# iTag3_sensors.net
KiCad netlist of a schematic drawn in Altium Designer
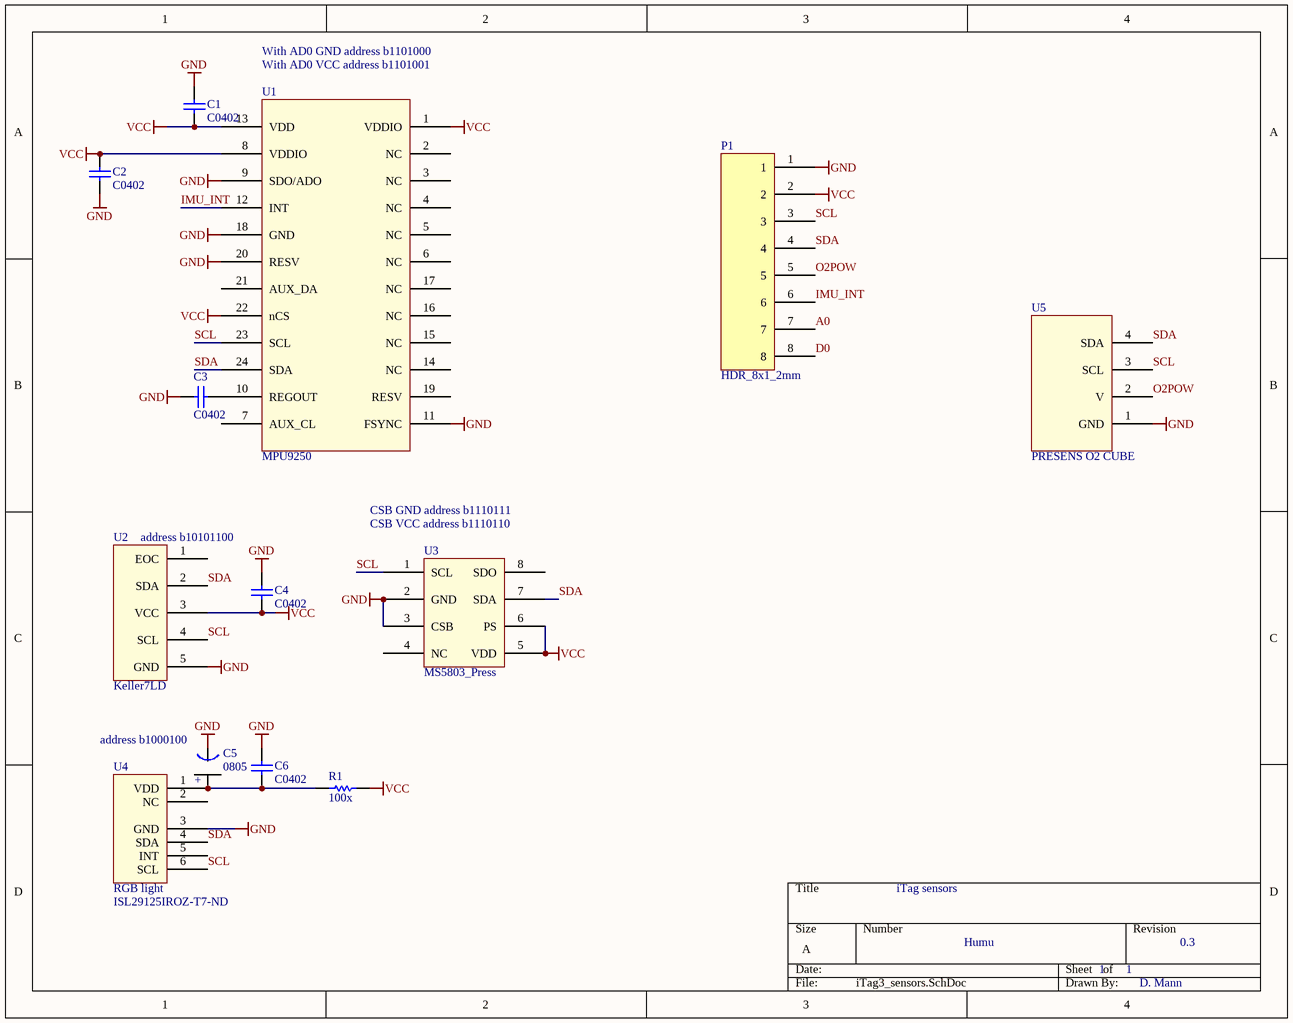
[diagram p0: iTag3_sensors.SchDoc]

(export (version "E")
  (design (tool "Eeschema 10.0.6"))
  (components
    (comp (ref "C1")
      (value "C0402")
      (footprint "0402")
      (description "Ceramic Chip Capacitor - Standard")
      (fields (field (name "PUBLISHER") "Altium Limited"))
      (libsource (lib "KEMET Chip Capacitor") (part "C0402"))
    )
    (comp (ref "C2")
      (value "C0402")
      (footprint "0402")
      (description "Ceramic Chip Capacitor - Standard")
      (fields (field (name "PUBLISHER") "Altium Limited"))
      (libsource (lib "KEMET Chip Capacitor") (part "C0402"))
    )
    (comp (ref "C3")
      (value "C0402")
      (footprint "0402")
      (description "Ceramic Chip Capacitor - Standard")
      (fields (field (name "PUBLISHER") "Altium Limited"))
      (libsource (lib "KEMET Chip Capacitor") (part "C0402"))
    )
    (comp (ref "C4")
      (value "C0402")
      (footprint "0402")
      (description "Ceramic Chip Capacitor - Standard")
      (fields (field (name "PUBLISHER") "Altium Limited"))
      (libsource (lib "KEMET Chip Capacitor") (part "C0402"))
    )
    (comp (ref "C5") (value "0805") (footprint "Tant0805") (libsource (lib "Loggerhead") (part "Tant0805")))
    (comp (ref "C6")
      (value "C0402")
      (footprint "0402")
      (description "Ceramic Chip Capacitor - Standard")
      (fields (field (name "PUBLISHER") "Altium Limited"))
      (libsource (lib "KEMET Chip Capacitor") (part "C0402"))
    )
    (comp (ref "P1")
      (value "HDR_8x1_2mm")
      (footprint "HDR_8x1_2mm")
      (libsource (lib "Loggerhead") (part "HDR_8x1_2mm"))
    )
    (comp (ref "R1")
      (value "100x")
      (footprint "3-0603")
      (fields (field (name "PUBLISHER") "Altium Limited"))
      (libsource (lib "Panasonic Resistor") (part "ERJ3RK"))
    )
    (comp (ref "U1")
      (value "MPU9250")
      (footprint "MPU6500")
      (description "Invensense")
      (libsource (lib "Loggerhead") (part "MPU-9250"))
    )
    (comp (ref "U2")
      (value "Keller7LD")
      (footprint "Keller7LD")
      (description "Keller Pressure/Temp")
      (libsource (lib "Loggerhead") (part "Keller 7LD"))
    )
    (comp (ref "U3")
      (value "MS5803_Press")
      (footprint "MS5803_Press")
      (libsource (lib "Loggerhead") (part "MS5803_Press"))
    )
    (comp (ref "U4")
      (value "RGB light")
      (footprint "ODFN")
      (description "RGB light sensor")
      (fields (field (name "SUPPLIER PART NUMBER 1") "ISL29125IROZ-T7-ND"))
      (libsource (lib "Loggerhead") (part "ISL29125"))
    )
    (comp (ref "U5")
      (value "PRESENS O2 CUBE")
      (footprint "PRESENS_O2")
      (libsource (lib "Loggerhead") (part "PRESENS_O2"))
    )
  )
  (nets
    (net (code "1") (name "/A0") (class "Default")
      (node (ref "P1") (pin "7") (pinfunction "7_7") (pintype "passive"))
    )
    (net (code "2") (name "/D0") (class "Default")
      (node (ref "P1") (pin "8") (pinfunction "8_8") (pintype "passive"))
    )
    (net (code "3") (name "/IMU_INT") (class "Default")
      (node (ref "P1") (pin "6") (pinfunction "6_6") (pintype "passive"))
      (node (ref "U1") (pin "12") (pinfunction "INT_12") (pintype "passive"))
    )
    (net (code "4") (name "/O2POW") (class "Default")
      (node (ref "P1") (pin "5") (pinfunction "5_5") (pintype "passive"))
      (node (ref "U5") (pin "2") (pinfunction "V_2") (pintype "passive"))
    )
    (net (code "5") (name "/SCL") (class "Default")
      (node (ref "P1") (pin "3") (pinfunction "3_3") (pintype "passive"))
      (node (ref "U1") (pin "23") (pinfunction "SCL_23") (pintype "passive"))
      (node (ref "U2") (pin "4") (pinfunction "SCL_4") (pintype "passive"))
      (node (ref "U3") (pin "1") (pinfunction "SCL_1") (pintype "passive"))
      (node (ref "U4") (pin "6") (pinfunction "SCL_6") (pintype "passive"))
      (node (ref "U5") (pin "3") (pinfunction "SCL_3") (pintype "passive"))
    )
    (net (code "6") (name "/SDA") (class "Default")
      (node (ref "P1") (pin "4") (pinfunction "4_4") (pintype "passive"))
      (node (ref "U1") (pin "24") (pinfunction "SDA_24") (pintype "passive"))
      (node (ref "U2") (pin "2") (pinfunction "SDA_2") (pintype "passive"))
      (node (ref "U3") (pin "7") (pinfunction "SDA_7") (pintype "passive"))
      (node (ref "U4") (pin "4") (pinfunction "SDA_4") (pintype "passive"))
      (node (ref "U5") (pin "4") (pinfunction "SDA_4") (pintype "passive"))
    )
    (net (code "7") (name "GND") (class "Default")
      (node (ref "C1") (pin "2") (pinfunction "2_2") (pintype "passive"))
      (node (ref "C2") (pin "2") (pinfunction "2_2") (pintype "passive"))
      (node (ref "C3") (pin "1") (pinfunction "1_1") (pintype "passive"))
      (node (ref "C4") (pin "2") (pinfunction "2_2") (pintype "passive"))
      (node (ref "C5") (pin "1") (pinfunction "GND_1") (pintype "passive"))
      (node (ref "C6") (pin "2") (pinfunction "2_2") (pintype "passive"))
      (node (ref "P1") (pin "1") (pinfunction "1_1") (pintype "passive"))
      (node (ref "U1") (pin "11") (pinfunction "FSYNC_11") (pintype "passive"))
      (node (ref "U1") (pin "18") (pinfunction "GND_18") (pintype "passive"))
      (node (ref "U1") (pin "20") (pinfunction "RESV_20") (pintype "passive"))
      (node (ref "U1") (pin "9") (pinfunction "SDO/ADO_9") (pintype "passive"))
      (node (ref "U2") (pin "5") (pinfunction "GND_5") (pintype "passive"))
      (node (ref "U3") (pin "2") (pinfunction "GND_2") (pintype "passive"))
      (node (ref "U3") (pin "3") (pinfunction "CSB_3") (pintype "passive"))
      (node (ref "U4") (pin "3") (pinfunction "GND_3") (pintype "passive"))
      (node (ref "U5") (pin "1") (pinfunction "GND_1") (pintype "passive"))
    )
    (net (code "8") (name "Net-(C5-+)") (class "Default")
      (node (ref "C5") (pin "2") (pinfunction "+_2") (pintype "passive"))
      (node (ref "C6") (pin "1") (pinfunction "1_1") (pintype "passive"))
      (node (ref "R1") (pin "2") (pinfunction "2_2") (pintype "passive"))
      (node (ref "U4") (pin "1") (pinfunction "VDD_1") (pintype "passive"))
    )
    (net (code "9") (name "Net-(U1-REGOUT)") (class "Default")
      (node (ref "C3") (pin "2") (pinfunction "2_2") (pintype "passive"))
      (node (ref "U1") (pin "10") (pinfunction "REGOUT_10") (pintype "passive"))
    )
    (net (code "10") (name "VCC") (class "Default")
      (node (ref "C1") (pin "1") (pinfunction "1_1") (pintype "passive"))
      (node (ref "C2") (pin "1") (pinfunction "1_1") (pintype "passive"))
      (node (ref "C4") (pin "1") (pinfunction "1_1") (pintype "passive"))
      (node (ref "P1") (pin "2") (pinfunction "2_2") (pintype "passive"))
      (node (ref "R1") (pin "1") (pinfunction "1_1") (pintype "passive"))
      (node (ref "U1") (pin "1") (pinfunction "VDDIO_1") (pintype "passive"))
      (node (ref "U1") (pin "13") (pinfunction "VDD_13") (pintype "passive"))
      (node (ref "U1") (pin "22") (pinfunction "nCS_22") (pintype "passive"))
      (node (ref "U1") (pin "8") (pinfunction "VDDIO_8") (pintype "passive"))
      (node (ref "U2") (pin "3") (pinfunction "VCC_3") (pintype "passive"))
      (node (ref "U3") (pin "5") (pinfunction "VDD_5") (pintype "power_in"))
      (node (ref "U3") (pin "6") (pinfunction "PS_6") (pintype "passive"))
    )
    (net (code "11") (name "unconnected-(U1-AUX_CL-Pad7)") (class "Default")
      (node (ref "U1") (pin "7") (pinfunction "AUX_CL_7") (pintype "passive"))
    )
    (net (code "12") (name "unconnected-(U1-AUX_DA-Pad21)") (class "Default")
      (node (ref "U1") (pin "21") (pinfunction "AUX_DA_21") (pintype "passive"))
    )
    (net (code "13") (name "unconnected-(U1-NC-Pad2)") (class "Default")
      (node (ref "U1") (pin "2") (pinfunction "NC_2") (pintype "passive"))
    )
    (net (code "14") (name "unconnected-(U1-NC-Pad3)") (class "Default")
      (node (ref "U1") (pin "3") (pinfunction "NC_3") (pintype "passive"))
    )
    (net (code "15") (name "unconnected-(U1-NC-Pad4)") (class "Default")
      (node (ref "U1") (pin "4") (pinfunction "NC_4") (pintype "passive"))
    )
    (net (code "16") (name "unconnected-(U1-NC-Pad5)") (class "Default")
      (node (ref "U1") (pin "5") (pinfunction "NC_5") (pintype "passive"))
    )
    (net (code "17") (name "unconnected-(U1-NC-Pad6)") (class "Default")
      (node (ref "U1") (pin "6") (pinfunction "NC_6") (pintype "passive"))
    )
    (net (code "18") (name "unconnected-(U1-NC-Pad14)") (class "Default")
      (node (ref "U1") (pin "14") (pinfunction "NC_14") (pintype "passive"))
    )
    (net (code "19") (name "unconnected-(U1-NC-Pad15)") (class "Default")
      (node (ref "U1") (pin "15") (pinfunction "NC_15") (pintype "passive"))
    )
    (net (code "20") (name "unconnected-(U1-NC-Pad16)") (class "Default")
      (node (ref "U1") (pin "16") (pinfunction "NC_16") (pintype "passive"))
    )
    (net (code "21") (name "unconnected-(U1-NC-Pad17)") (class "Default")
      (node (ref "U1") (pin "17") (pinfunction "NC_17") (pintype "passive"))
    )
    (net (code "22") (name "unconnected-(U1-RESV-Pad19)") (class "Default")
      (node (ref "U1") (pin "19") (pinfunction "RESV_19") (pintype "passive"))
    )
    (net (code "23") (name "unconnected-(U2-EOC-Pad1)") (class "Default")
      (node (ref "U2") (pin "1") (pinfunction "EOC_1") (pintype "passive"))
    )
    (net (code "24") (name "unconnected-(U3-NC-Pad4)") (class "Default")
      (node (ref "U3") (pin "4") (pinfunction "NC_4") (pintype "passive"))
    )
    (net (code "25") (name "unconnected-(U3-SDO-Pad8)") (class "Default")
      (node (ref "U3") (pin "8") (pinfunction "SDO_8") (pintype "passive"))
    )
    (net (code "26") (name "unconnected-(U4-INT-Pad5)") (class "Default")
      (node (ref "U4") (pin "5") (pinfunction "INT_5") (pintype "passive"))
    )
    (net (code "27") (name "unconnected-(U4-NC-Pad2)") (class "Default")
      (node (ref "U4") (pin "2") (pinfunction "NC_2") (pintype "passive"))
    )
  )
)
